# bottom.net
KiCad netlist of a schematic drawn in EAGLE
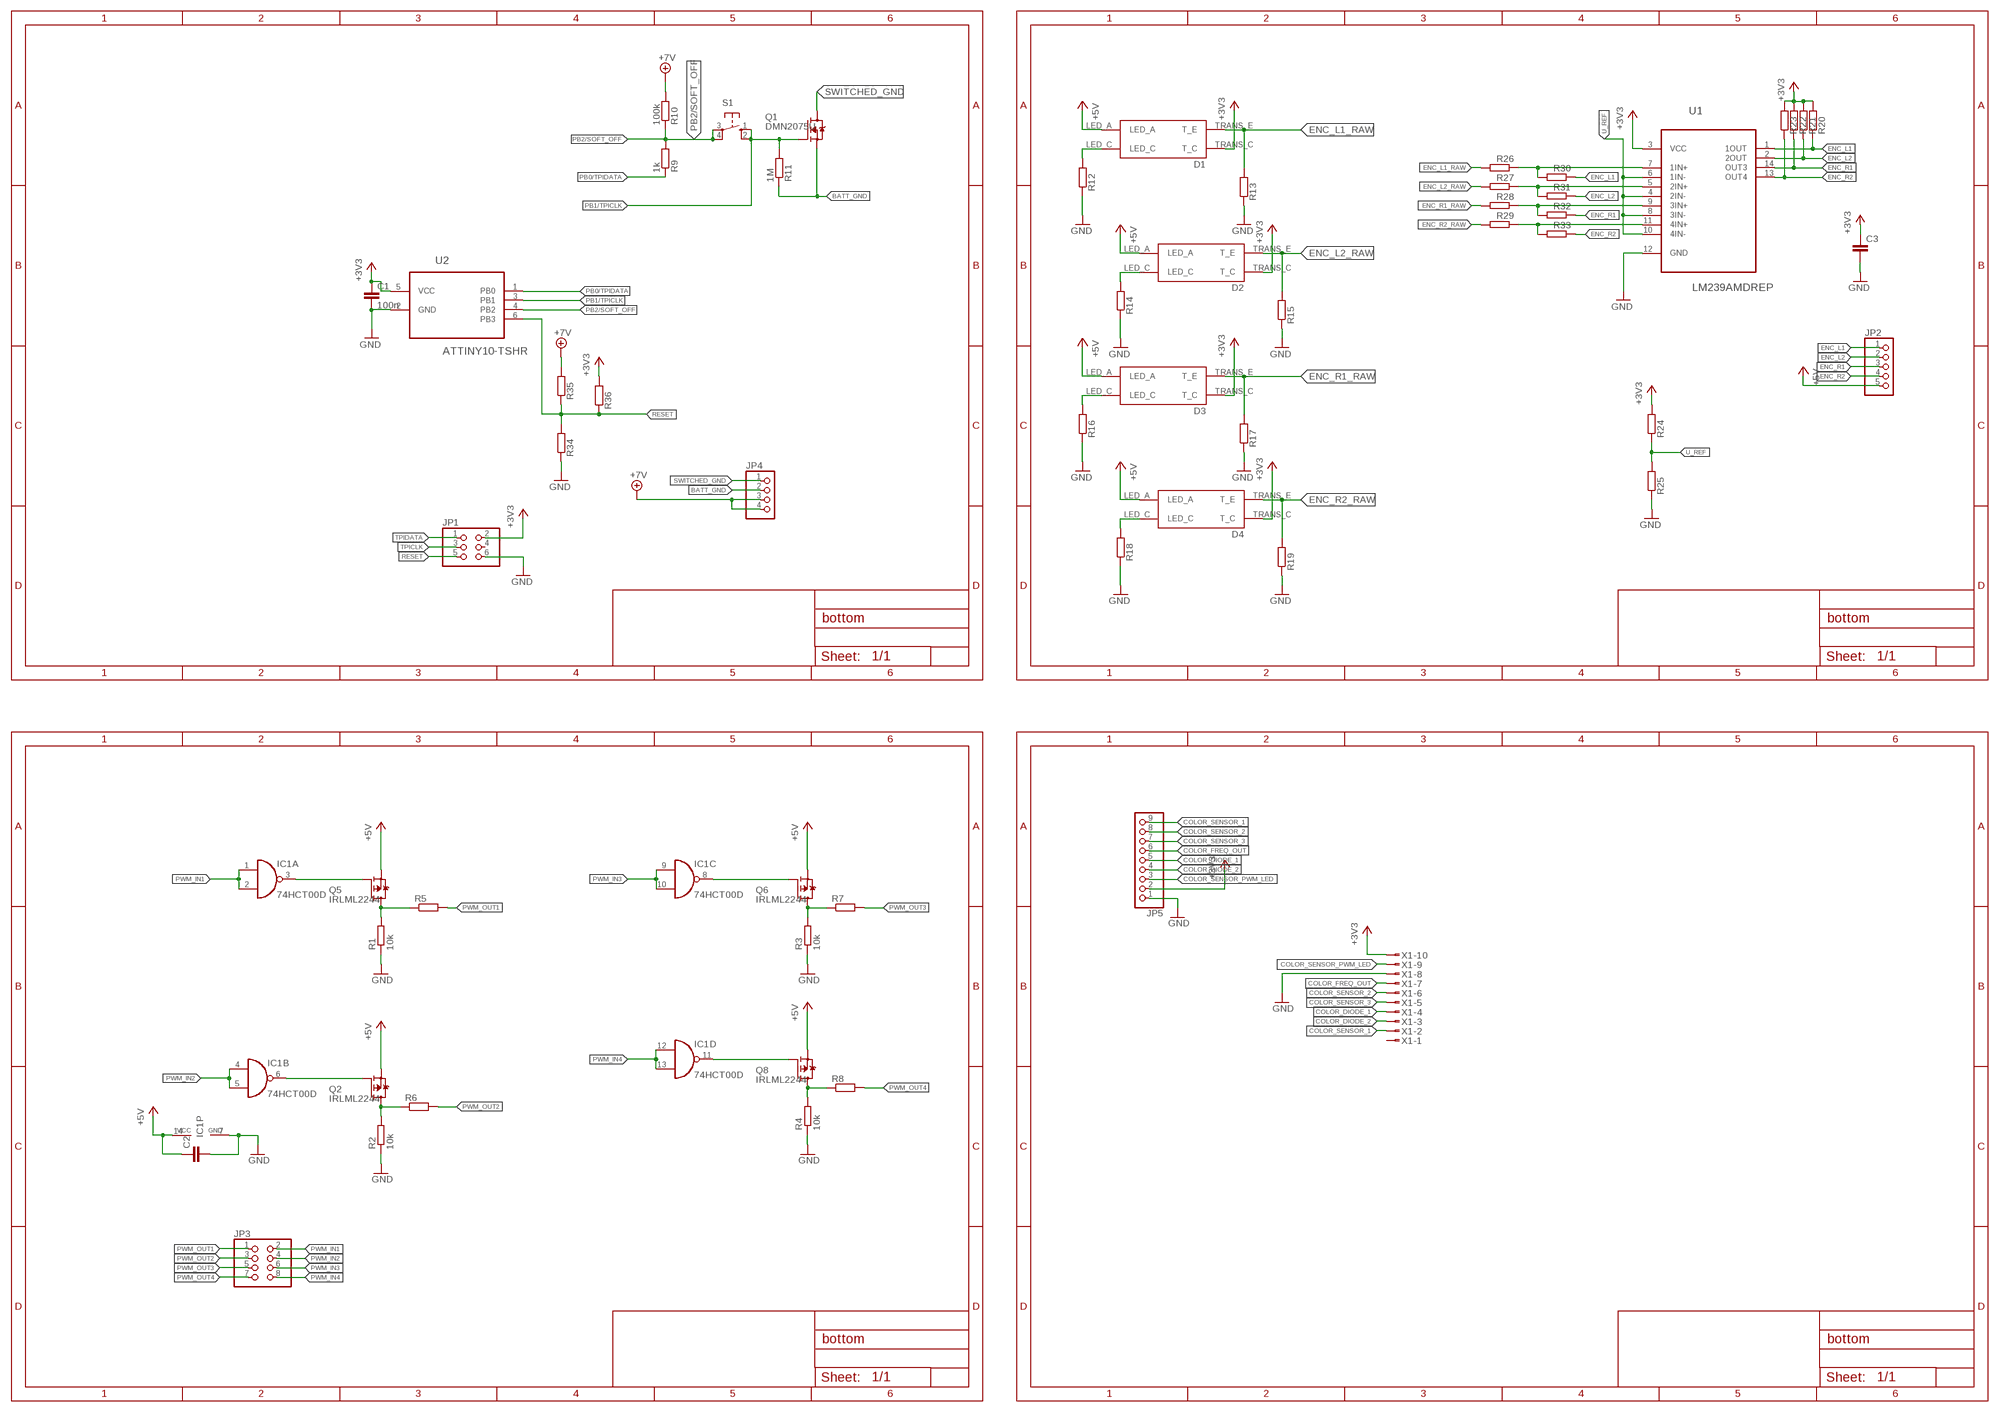
[diagram p0: schematic, sheet 1]

(export (version "E")
  (design (tool "Eeschema 10.0.6"))
  (components
    (comp (ref "C1")
      (value "100n")
      (footprint "eagle-import:C0603")
      (libsource (lib "eagle-import") (part "C-EUC0603"))
    )
    (comp (ref "C2")
      (value "C-EUC0603")
      (footprint "eagle-import:C0603")
      (libsource (lib "eagle-import") (part "C-EUC0603"))
    )
    (comp (ref "C3")
      (value "C-EUC0603")
      (footprint "eagle-import:C0603")
      (libsource (lib "eagle-import") (part "C-EUC0603"))
    )
    (comp (ref "D1")
      (value "CNY70")
      (footprint "eagle-import:CNY70")
      (libsource (lib "eagle-import") (part "CNY70"))
    )
    (comp (ref "D2")
      (value "CNY70")
      (footprint "eagle-import:CNY70")
      (libsource (lib "eagle-import") (part "CNY70"))
    )
    (comp (ref "D3")
      (value "CNY70")
      (footprint "eagle-import:CNY70")
      (libsource (lib "eagle-import") (part "CNY70"))
    )
    (comp (ref "D4")
      (value "CNY70")
      (footprint "eagle-import:CNY70")
      (libsource (lib "eagle-import") (part "CNY70"))
    )
    (comp (ref "IC1")
      (value "74HCT00D")
      (footprint "eagle-import:SO14")
      (libsource (lib "eagle-import") (part "7400DHCT"))
    )
    (comp (ref "JP1")
      (value "PINHD-2X3")
      (footprint "eagle-import:2X03")
      (libsource (lib "eagle-import") (part "PINHD-2X3"))
    )
    (comp (ref "JP2")
      (value "PINHD-1X5")
      (footprint "eagle-import:1X05")
      (libsource (lib "eagle-import") (part "PINHD-1X5"))
    )
    (comp (ref "JP3")
      (value "PINHD-2X4")
      (footprint "eagle-import:2X04")
      (libsource (lib "eagle-import") (part "PINHD-2X4"))
    )
    (comp (ref "JP4")
      (value "PINHD-1X4")
      (footprint "eagle-import:1X04")
      (libsource (lib "eagle-import") (part "PINHD-1X4"))
    )
    (comp (ref "JP5")
      (value "PINHD-1X9")
      (footprint "eagle-import:1X09")
      (libsource (lib "eagle-import") (part "PINHD-1X9"))
    )
    (comp (ref "Q1")
      (value "DMN2075U")
      (footprint "eagle-import:SOT95P240X112-3N")
      (libsource (lib "eagle-import") (part "DMN2075U"))
    )
    (comp (ref "Q2")
      (value "IRLML2244")
      (footprint "eagle-import:SOT95P240X112-3N")
      (libsource (lib "eagle-import") (part "IRLML2244"))
    )
    (comp (ref "Q5")
      (value "IRLML2244")
      (footprint "eagle-import:SOT95P240X112-3N")
      (libsource (lib "eagle-import") (part "IRLML2244"))
    )
    (comp (ref "Q6")
      (value "IRLML2244")
      (footprint "eagle-import:SOT95P240X112-3N")
      (libsource (lib "eagle-import") (part "IRLML2244"))
    )
    (comp (ref "Q8")
      (value "IRLML2244")
      (footprint "eagle-import:SOT95P240X112-3N")
      (libsource (lib "eagle-import") (part "IRLML2244"))
    )
    (comp (ref "R1")
      (value "10k")
      (footprint "eagle-import:R0603")
      (libsource (lib "eagle-import") (part "R-EU_R0603"))
    )
    (comp (ref "R2")
      (value "10k")
      (footprint "eagle-import:R0603")
      (libsource (lib "eagle-import") (part "R-EU_R0603"))
    )
    (comp (ref "R3")
      (value "10k")
      (footprint "eagle-import:R0603")
      (libsource (lib "eagle-import") (part "R-EU_R0603"))
    )
    (comp (ref "R4")
      (value "10k")
      (footprint "eagle-import:R0603")
      (libsource (lib "eagle-import") (part "R-EU_R0603"))
    )
    (comp (ref "R5")
      (value "R-EU_M0805")
      (footprint "eagle-import:M0805")
      (libsource (lib "eagle-import") (part "R-EU_M0805"))
    )
    (comp (ref "R6")
      (value "R-EU_M0805")
      (footprint "eagle-import:M0805")
      (libsource (lib "eagle-import") (part "R-EU_M0805"))
    )
    (comp (ref "R7")
      (value "R-EU_M0805")
      (footprint "eagle-import:M0805")
      (libsource (lib "eagle-import") (part "R-EU_M0805"))
    )
    (comp (ref "R8")
      (value "R-EU_M0805")
      (footprint "eagle-import:M0805")
      (libsource (lib "eagle-import") (part "R-EU_M0805"))
    )
    (comp (ref "R9")
      (value "1k")
      (footprint "eagle-import:M0805")
      (libsource (lib "eagle-import") (part "R-EU_M0805"))
    )
    (comp (ref "R10")
      (value "100k")
      (footprint "eagle-import:M0805")
      (libsource (lib "eagle-import") (part "R-EU_M0805"))
    )
    (comp (ref "R11")
      (value "1M")
      (footprint "eagle-import:M0805")
      (libsource (lib "eagle-import") (part "R-EU_M0805"))
    )
    (comp (ref "R12")
      (value "R-EU_R0805")
      (footprint "eagle-import:R0805")
      (libsource (lib "eagle-import") (part "R-EU_R0805"))
    )
    (comp (ref "R13")
      (value "R-EU_M0805")
      (footprint "eagle-import:M0805")
      (libsource (lib "eagle-import") (part "R-EU_M0805"))
    )
    (comp (ref "R14")
      (value "R-EU_M0805")
      (footprint "eagle-import:M0805")
      (libsource (lib "eagle-import") (part "R-EU_M0805"))
    )
    (comp (ref "R15")
      (value "R-EU_M0805")
      (footprint "eagle-import:M0805")
      (libsource (lib "eagle-import") (part "R-EU_M0805"))
    )
    (comp (ref "R16")
      (value "R-EU_M0805")
      (footprint "eagle-import:M0805")
      (libsource (lib "eagle-import") (part "R-EU_M0805"))
    )
    (comp (ref "R17")
      (value "R-EU_M0805")
      (footprint "eagle-import:M0805")
      (libsource (lib "eagle-import") (part "R-EU_M0805"))
    )
    (comp (ref "R18")
      (value "R-EU_M0805")
      (footprint "eagle-import:M0805")
      (libsource (lib "eagle-import") (part "R-EU_M0805"))
    )
    (comp (ref "R19")
      (value "R-EU_M0805")
      (footprint "eagle-import:M0805")
      (libsource (lib "eagle-import") (part "R-EU_M0805"))
    )
    (comp (ref "R20")
      (value "R-EU_M0805")
      (footprint "eagle-import:M0805")
      (libsource (lib "eagle-import") (part "R-EU_M0805"))
    )
    (comp (ref "R21")
      (value "R-EU_M0805")
      (footprint "eagle-import:M0805")
      (libsource (lib "eagle-import") (part "R-EU_M0805"))
    )
    (comp (ref "R22")
      (value "R-EU_M0805")
      (footprint "eagle-import:M0805")
      (libsource (lib "eagle-import") (part "R-EU_M0805"))
    )
    (comp (ref "R23")
      (value "R-EU_M0805")
      (footprint "eagle-import:M0805")
      (libsource (lib "eagle-import") (part "R-EU_M0805"))
    )
    (comp (ref "R24")
      (value "R-EU_M0805")
      (footprint "eagle-import:M0805")
      (libsource (lib "eagle-import") (part "R-EU_M0805"))
    )
    (comp (ref "R25")
      (value "R-EU_M0805")
      (footprint "eagle-import:M0805")
      (libsource (lib "eagle-import") (part "R-EU_M0805"))
    )
    (comp (ref "R26")
      (value "R-EU_M0805")
      (footprint "eagle-import:M0805")
      (libsource (lib "eagle-import") (part "R-EU_M0805"))
    )
    (comp (ref "R27")
      (value "R-EU_M0805")
      (footprint "eagle-import:M0805")
      (libsource (lib "eagle-import") (part "R-EU_M0805"))
    )
    (comp (ref "R28")
      (value "R-EU_M0805")
      (footprint "eagle-import:M0805")
      (libsource (lib "eagle-import") (part "R-EU_M0805"))
    )
    (comp (ref "R29")
      (value "R-EU_M0805")
      (footprint "eagle-import:M0805")
      (libsource (lib "eagle-import") (part "R-EU_M0805"))
    )
    (comp (ref "R30")
      (value "R-EU_M0805")
      (footprint "eagle-import:M0805")
      (libsource (lib "eagle-import") (part "R-EU_M0805"))
    )
    (comp (ref "R31")
      (value "R-EU_M0805")
      (footprint "eagle-import:M0805")
      (libsource (lib "eagle-import") (part "R-EU_M0805"))
    )
    (comp (ref "R32")
      (value "R-EU_M0805")
      (footprint "eagle-import:M0805")
      (libsource (lib "eagle-import") (part "R-EU_M0805"))
    )
    (comp (ref "R33")
      (value "R-EU_M0805")
      (footprint "eagle-import:M0805")
      (libsource (lib "eagle-import") (part "R-EU_M0805"))
    )
    (comp (ref "R34")
      (value "R-EU_M0805")
      (footprint "eagle-import:M0805")
      (libsource (lib "eagle-import") (part "R-EU_M0805"))
    )
    (comp (ref "R35")
      (value "R-EU_M0805")
      (footprint "eagle-import:M0805")
      (libsource (lib "eagle-import") (part "R-EU_M0805"))
    )
    (comp (ref "R36")
      (value "R-EU_M0805")
      (footprint "eagle-import:M0805")
      (libsource (lib "eagle-import") (part "R-EU_M0805"))
    )
    (comp (ref "S1")
      (value "10-XX")
      (footprint "eagle-import:B3F-10XX")
      (fields (field (name "MPN") "B3F-1000"))
      (libsource (lib "eagle-import") (part "10-XX"))
    )
    (comp (ref "U1")
      (value "LM239AMDREP")
      (footprint "eagle-import:SOIC127P600X175-14N")
      (libsource (lib "eagle-import") (part "LM239AMDREP"))
    )
    (comp (ref "U2")
      (value "ATTINY10-TSHR")
      (footprint "eagle-import:SOT95P280X145-6N")
      (libsource (lib "eagle-import") (part "ATTINY10-TSHR"))
    )
    (comp (ref "X1")
      (value "FTOP-10")
      (footprint "eagle-import:FTOP-10")
      (libsource (lib "eagle-import") (part "FTOP-10"))
    )
  )
  (nets
    (net (code "1") (name "+3V3") (class "Default")
      (node (ref "C1") (pin "1") (pinfunction "1_1") (pintype "passive"))
      (node (ref "C3") (pin "1") (pinfunction "1_1") (pintype "passive"))
      (node (ref "D1") (pin "TRANS_C") (pinfunction "T_C_TRANS_C") (pintype "bidirectional"))
      (node (ref "D2") (pin "TRANS_C") (pinfunction "T_C_TRANS_C") (pintype "bidirectional"))
      (node (ref "D3") (pin "TRANS_C") (pinfunction "T_C_TRANS_C") (pintype "bidirectional"))
      (node (ref "D4") (pin "TRANS_C") (pinfunction "T_C_TRANS_C") (pintype "bidirectional"))
      (node (ref "JP1") (pin "2") (pinfunction "2_2") (pintype "passive"))
      (node (ref "JP5") (pin "2") (pinfunction "2_2") (pintype "passive"))
      (node (ref "R20") (pin "2") (pinfunction "2_2") (pintype "passive"))
      (node (ref "R21") (pin "2") (pinfunction "2_2") (pintype "passive"))
      (node (ref "R22") (pin "2") (pinfunction "2_2") (pintype "passive"))
      (node (ref "R23") (pin "2") (pinfunction "2_2") (pintype "passive"))
      (node (ref "R24") (pin "2") (pinfunction "2_2") (pintype "passive"))
      (node (ref "R36") (pin "2") (pinfunction "2_2") (pintype "passive"))
      (node (ref "U1") (pin "3") (pinfunction "VCC_3") (pintype "power_in"))
      (node (ref "U2") (pin "5") (pinfunction "VCC_5") (pintype "power_in"))
      (node (ref "X1") (pin "10") (pinfunction "1_10") (pintype "passive"))
    )
    (net (code "2") (name "+5V") (class "Default")
      (node (ref "C2") (pin "1") (pinfunction "1_1") (pintype "passive"))
      (node (ref "D1") (pin "LED_A") (pinfunction "LED_A_LED_A") (pintype "bidirectional"))
      (node (ref "D2") (pin "LED_A") (pinfunction "LED_A_LED_A") (pintype "bidirectional"))
      (node (ref "D3") (pin "LED_A") (pinfunction "LED_A_LED_A") (pintype "bidirectional"))
      (node (ref "D4") (pin "LED_A") (pinfunction "LED_A_LED_A") (pintype "bidirectional"))
      (node (ref "IC1") (pin "14") (pinfunction "VCC_14") (pintype "power_in"))
      (node (ref "JP2") (pin "5") (pinfunction "5_5") (pintype "passive"))
      (node (ref "Q2") (pin "S") (pinfunction "S_S") (pintype "passive"))
      (node (ref "Q5") (pin "S") (pinfunction "S_S") (pintype "passive"))
      (node (ref "Q6") (pin "S") (pinfunction "S_S") (pintype "passive"))
      (node (ref "Q8") (pin "S") (pinfunction "S_S") (pintype "passive"))
    )
    (net (code "3") (name "+7V") (class "Default")
      (node (ref "JP4") (pin "3") (pinfunction "3_3") (pintype "passive"))
      (node (ref "JP4") (pin "4") (pinfunction "4_4") (pintype "passive"))
      (node (ref "R10") (pin "2") (pinfunction "2_2") (pintype "passive"))
      (node (ref "R35") (pin "2") (pinfunction "2_2") (pintype "passive"))
    )
    (net (code "4") (name "BATT_GND") (class "Default")
      (node (ref "JP4") (pin "2") (pinfunction "2_2") (pintype "passive"))
      (node (ref "Q1") (pin "S") (pinfunction "S_S") (pintype "passive"))
      (node (ref "R11") (pin "1") (pinfunction "1_1") (pintype "passive"))
    )
    (net (code "5") (name "COLOR_DIODE_1") (class "Default")
      (node (ref "JP5") (pin "5") (pinfunction "5_5") (pintype "passive"))
      (node (ref "X1") (pin "4") (pinfunction "1_4") (pintype "passive"))
    )
    (net (code "6") (name "COLOR_DIODE_2") (class "Default")
      (node (ref "JP5") (pin "4") (pinfunction "4_4") (pintype "passive"))
      (node (ref "X1") (pin "3") (pinfunction "1_3") (pintype "passive"))
    )
    (net (code "7") (name "COLOR_FREQ_OUT") (class "Default")
      (node (ref "JP5") (pin "6") (pinfunction "6_6") (pintype "passive"))
      (node (ref "X1") (pin "7") (pinfunction "1_7") (pintype "passive"))
    )
    (net (code "8") (name "COLOR_SENSOR_1") (class "Default")
      (node (ref "JP5") (pin "9") (pinfunction "9_9") (pintype "passive"))
      (node (ref "X1") (pin "2") (pinfunction "1_2") (pintype "passive"))
    )
    (net (code "9") (name "COLOR_SENSOR_2") (class "Default")
      (node (ref "JP5") (pin "8") (pinfunction "8_8") (pintype "passive"))
      (node (ref "X1") (pin "6") (pinfunction "1_6") (pintype "passive"))
    )
    (net (code "10") (name "COLOR_SENSOR_3") (class "Default")
      (node (ref "JP5") (pin "7") (pinfunction "7_7") (pintype "passive"))
      (node (ref "X1") (pin "5") (pinfunction "1_5") (pintype "passive"))
    )
    (net (code "11") (name "COLOR_SENSOR_PWM_LED") (class "Default")
      (node (ref "JP5") (pin "3") (pinfunction "3_3") (pintype "passive"))
      (node (ref "X1") (pin "9") (pinfunction "1_9") (pintype "passive"))
    )
    (net (code "12") (name "ENC_L1") (class "Default")
      (node (ref "JP2") (pin "1") (pinfunction "1_1") (pintype "passive"))
      (node (ref "R20") (pin "1") (pinfunction "1_1") (pintype "passive"))
      (node (ref "R30") (pin "1") (pinfunction "1_1") (pintype "passive"))
      (node (ref "U1") (pin "1") (pinfunction "1OUT_1") (pintype "output"))
    )
    (net (code "13") (name "ENC_L1_RAW") (class "Default")
      (node (ref "D1") (pin "TRANS_E") (pinfunction "T_E_TRANS_E") (pintype "bidirectional"))
      (node (ref "R13") (pin "2") (pinfunction "2_2") (pintype "passive"))
      (node (ref "R26") (pin "2") (pinfunction "2_2") (pintype "passive"))
    )
    (net (code "14") (name "ENC_L2") (class "Default")
      (node (ref "JP2") (pin "2") (pinfunction "2_2") (pintype "passive"))
      (node (ref "R21") (pin "1") (pinfunction "1_1") (pintype "passive"))
      (node (ref "R31") (pin "1") (pinfunction "1_1") (pintype "passive"))
      (node (ref "U1") (pin "2") (pinfunction "2OUT_2") (pintype "output"))
    )
    (net (code "15") (name "ENC_L2_RAW") (class "Default")
      (node (ref "D2") (pin "TRANS_E") (pinfunction "T_E_TRANS_E") (pintype "bidirectional"))
      (node (ref "R15") (pin "2") (pinfunction "2_2") (pintype "passive"))
      (node (ref "R27") (pin "2") (pinfunction "2_2") (pintype "passive"))
    )
    (net (code "16") (name "ENC_R1") (class "Default")
      (node (ref "JP2") (pin "3") (pinfunction "3_3") (pintype "passive"))
      (node (ref "R22") (pin "1") (pinfunction "1_1") (pintype "passive"))
      (node (ref "R32") (pin "1") (pinfunction "1_1") (pintype "passive"))
      (node (ref "U1") (pin "14") (pinfunction "OUT3_14") (pintype "output"))
    )
    (net (code "17") (name "ENC_R1_RAW") (class "Default")
      (node (ref "D3") (pin "TRANS_E") (pinfunction "T_E_TRANS_E") (pintype "bidirectional"))
      (node (ref "R17") (pin "2") (pinfunction "2_2") (pintype "passive"))
      (node (ref "R28") (pin "2") (pinfunction "2_2") (pintype "passive"))
    )
    (net (code "18") (name "ENC_R2") (class "Default")
      (node (ref "JP2") (pin "4") (pinfunction "4_4") (pintype "passive"))
      (node (ref "R23") (pin "1") (pinfunction "1_1") (pintype "passive"))
      (node (ref "R33") (pin "1") (pinfunction "1_1") (pintype "passive"))
      (node (ref "U1") (pin "13") (pinfunction "OUT4_13") (pintype "output"))
    )
    (net (code "19") (name "ENC_R2_RAW") (class "Default")
      (node (ref "D4") (pin "TRANS_E") (pinfunction "T_E_TRANS_E") (pintype "bidirectional"))
      (node (ref "R19") (pin "2") (pinfunction "2_2") (pintype "passive"))
      (node (ref "R29") (pin "2") (pinfunction "2_2") (pintype "passive"))
    )
    (net (code "20") (name "GND") (class "Default")
      (node (ref "C1") (pin "2") (pinfunction "2_2") (pintype "passive"))
      (node (ref "C2") (pin "2") (pinfunction "2_2") (pintype "passive"))
      (node (ref "C3") (pin "2") (pinfunction "2_2") (pintype "passive"))
      (node (ref "IC1") (pin "7") (pinfunction "GND_7") (pintype "power_in"))
      (node (ref "JP1") (pin "6") (pinfunction "6_6") (pintype "passive"))
      (node (ref "JP5") (pin "1") (pinfunction "1_1") (pintype "passive"))
      (node (ref "R1") (pin "1") (pinfunction "1_1") (pintype "passive"))
      (node (ref "R12") (pin "1") (pinfunction "1_1") (pintype "passive"))
      (node (ref "R13") (pin "1") (pinfunction "1_1") (pintype "passive"))
      (node (ref "R14") (pin "1") (pinfunction "1_1") (pintype "passive"))
      (node (ref "R15") (pin "1") (pinfunction "1_1") (pintype "passive"))
      (node (ref "R16") (pin "1") (pinfunction "1_1") (pintype "passive"))
      (node (ref "R17") (pin "1") (pinfunction "1_1") (pintype "passive"))
      (node (ref "R18") (pin "1") (pinfunction "1_1") (pintype "passive"))
      (node (ref "R19") (pin "1") (pinfunction "1_1") (pintype "passive"))
      (node (ref "R2") (pin "1") (pinfunction "1_1") (pintype "passive"))
      (node (ref "R25") (pin "1") (pinfunction "1_1") (pintype "passive"))
      (node (ref "R3") (pin "1") (pinfunction "1_1") (pintype "passive"))
      (node (ref "R34") (pin "1") (pinfunction "1_1") (pintype "passive"))
      (node (ref "R4") (pin "1") (pinfunction "1_1") (pintype "passive"))
      (node (ref "U1") (pin "12") (pinfunction "GND_12") (pintype "passive"))
      (node (ref "U2") (pin "2") (pinfunction "GND_2") (pintype "passive"))
      (node (ref "X1") (pin "8") (pinfunction "1_8") (pintype "passive"))
    )
    (net (code "21") (name "Net-(D1-PadLED_C)") (class "Default")
      (node (ref "D1") (pin "LED_C") (pinfunction "LED_C_LED_C") (pintype "bidirectional"))
      (node (ref "R12") (pin "2") (pinfunction "2_2") (pintype "passive"))
    )
    (net (code "22") (name "Net-(D2-PadLED_C)") (class "Default")
      (node (ref "D2") (pin "LED_C") (pinfunction "LED_C_LED_C") (pintype "bidirectional"))
      (node (ref "R14") (pin "2") (pinfunction "2_2") (pintype "passive"))
    )
    (net (code "23") (name "Net-(D3-PadLED_C)") (class "Default")
      (node (ref "D3") (pin "LED_C") (pinfunction "LED_C_LED_C") (pintype "bidirectional"))
      (node (ref "R16") (pin "2") (pinfunction "2_2") (pintype "passive"))
    )
    (net (code "24") (name "Net-(D4-PadLED_C)") (class "Default")
      (node (ref "D4") (pin "LED_C") (pinfunction "LED_C_LED_C") (pintype "bidirectional"))
      (node (ref "R18") (pin "2") (pinfunction "2_2") (pintype "passive"))
    )
    (net (code "25") (name "Net-(IC1A-O)") (class "Default")
      (node (ref "IC1") (pin "3") (pinfunction "O_3") (pintype "output"))
      (node (ref "Q5") (pin "G") (pinfunction "G_G") (pintype "passive"))
    )
    (net (code "26") (name "Net-(IC1B-O)") (class "Default")
      (node (ref "IC1") (pin "6") (pinfunction "O_6") (pintype "output"))
      (node (ref "Q2") (pin "G") (pinfunction "G_G") (pintype "passive"))
    )
    (net (code "27") (name "Net-(IC1C-O)") (class "Default")
      (node (ref "IC1") (pin "8") (pinfunction "O_8") (pintype "output"))
      (node (ref "Q6") (pin "G") (pinfunction "G_G") (pintype "passive"))
    )
    (net (code "28") (name "Net-(IC1D-O)") (class "Default")
      (node (ref "IC1") (pin "11") (pinfunction "O_11") (pintype "output"))
      (node (ref "Q8") (pin "G") (pinfunction "G_G") (pintype "passive"))
    )
    (net (code "29") (name "Net-(Q2-PadD)") (class "Default")
      (node (ref "Q2") (pin "D") (pinfunction "D_D") (pintype "passive"))
      (node (ref "R2") (pin "2") (pinfunction "2_2") (pintype "passive"))
      (node (ref "R6") (pin "1") (pinfunction "1_1") (pintype "passive"))
    )
    (net (code "30") (name "Net-(Q5-PadD)") (class "Default")
      (node (ref "Q5") (pin "D") (pinfunction "D_D") (pintype "passive"))
      (node (ref "R1") (pin "2") (pinfunction "2_2") (pintype "passive"))
      (node (ref "R5") (pin "1") (pinfunction "1_1") (pintype "passive"))
    )
    (net (code "31") (name "Net-(Q6-PadD)") (class "Default")
      (node (ref "Q6") (pin "D") (pinfunction "D_D") (pintype "passive"))
      (node (ref "R3") (pin "2") (pinfunction "2_2") (pintype "passive"))
      (node (ref "R7") (pin "1") (pinfunction "1_1") (pintype "passive"))
    )
    (net (code "32") (name "Net-(Q8-PadD)") (class "Default")
      (node (ref "Q8") (pin "D") (pinfunction "D_D") (pintype "passive"))
      (node (ref "R4") (pin "2") (pinfunction "2_2") (pintype "passive"))
      (node (ref "R8") (pin "1") (pinfunction "1_1") (pintype "passive"))
    )
    (net (code "33") (name "Net-(U1-1IN+)") (class "Default")
      (node (ref "R26") (pin "1") (pinfunction "1_1") (pintype "passive"))
      (node (ref "R30") (pin "2") (pinfunction "2_2") (pintype "passive"))
      (node (ref "U1") (pin "7") (pinfunction "1IN+_7") (pintype "input"))
    )
    (net (code "34") (name "Net-(U1-2IN+)") (class "Default")
      (node (ref "R27") (pin "1") (pinfunction "1_1") (pintype "passive"))
      (node (ref "R31") (pin "2") (pinfunction "2_2") (pintype "passive"))
      (node (ref "U1") (pin "5") (pinfunction "2IN+_5") (pintype "input"))
    )
    (net (code "35") (name "Net-(U1-3IN+)") (class "Default")
      (node (ref "R28") (pin "1") (pinfunction "1_1") (pintype "passive"))
      (node (ref "R32") (pin "2") (pinfunction "2_2") (pintype "passive"))
      (node (ref "U1") (pin "9") (pinfunction "3IN+_9") (pintype "input"))
    )
    (net (code "36") (name "Net-(U1-4IN+)") (class "Default")
      (node (ref "R29") (pin "1") (pinfunction "1_1") (pintype "passive"))
      (node (ref "R33") (pin "2") (pinfunction "2_2") (pintype "passive"))
      (node (ref "U1") (pin "11") (pinfunction "4IN+_11") (pintype "input"))
    )
    (net (code "37") (name "PB0{slash}TPIDATA") (class "Default")
      (node (ref "R9") (pin "1") (pinfunction "1_1") (pintype "passive"))
      (node (ref "U2") (pin "1") (pinfunction "PB0_1") (pintype "bidirectional"))
    )
    (net (code "38") (name "PB1{slash}TPICLK") (class "Default")
      (node (ref "Q1") (pin "G") (pinfunction "G_G") (pintype "passive"))
      (node (ref "R11") (pin "2") (pinfunction "2_2") (pintype "passive"))
      (node (ref "S1") (pin "1") (pinfunction "S_1") (pintype "passive"))
      (node (ref "S1") (pin "2") (pinfunction "S1_2") (pintype "passive"))
      (node (ref "U2") (pin "3") (pinfunction "PB1_3") (pintype "bidirectional"))
    )
    (net (code "39") (name "PB2{slash}SOFT_OFF") (class "Default")
      (node (ref "R10") (pin "1") (pinfunction "1_1") (pintype "passive"))
      (node (ref "R9") (pin "2") (pinfunction "2_2") (pintype "passive"))
      (node (ref "S1") (pin "3") (pinfunction "P_3") (pintype "passive"))
      (node (ref "S1") (pin "4") (pinfunction "P1_4") (pintype "passive"))
      (node (ref "U2") (pin "4") (pinfunction "PB2_4") (pintype "bidirectional"))
    )
    (net (code "40") (name "PWM_IN1") (class "Default")
      (node (ref "IC1") (pin "1") (pinfunction "I0_1") (pintype "input"))
      (node (ref "IC1") (pin "2") (pinfunction "I1_2") (pintype "input"))
      (node (ref "JP3") (pin "2") (pinfunction "2_2") (pintype "passive"))
    )
    (net (code "41") (name "PWM_IN2") (class "Default")
      (node (ref "IC1") (pin "4") (pinfunction "I0_4") (pintype "input"))
      (node (ref "IC1") (pin "5") (pinfunction "I1_5") (pintype "input"))
      (node (ref "JP3") (pin "4") (pinfunction "4_4") (pintype "passive"))
    )
    (net (code "42") (name "PWM_IN3") (class "Default")
      (node (ref "IC1") (pin "10") (pinfunction "I1_10") (pintype "input"))
      (node (ref "IC1") (pin "9") (pinfunction "I0_9") (pintype "input"))
      (node (ref "JP3") (pin "6") (pinfunction "6_6") (pintype "passive"))
    )
    (net (code "43") (name "PWM_IN4") (class "Default")
      (node (ref "IC1") (pin "12") (pinfunction "I0_12") (pintype "input"))
      (node (ref "IC1") (pin "13") (pinfunction "I1_13") (pintype "input"))
      (node (ref "JP3") (pin "8") (pinfunction "8_8") (pintype "passive"))
    )
    (net (code "44") (name "PWM_OUT1") (class "Default")
      (node (ref "JP3") (pin "1") (pinfunction "1_1") (pintype "passive"))
      (node (ref "R5") (pin "2") (pinfunction "2_2") (pintype "passive"))
    )
    (net (code "45") (name "PWM_OUT2") (class "Default")
      (node (ref "JP3") (pin "3") (pinfunction "3_3") (pintype "passive"))
      (node (ref "R6") (pin "2") (pinfunction "2_2") (pintype "passive"))
    )
    (net (code "46") (name "PWM_OUT3") (class "Default")
      (node (ref "JP3") (pin "5") (pinfunction "5_5") (pintype "passive"))
      (node (ref "R7") (pin "2") (pinfunction "2_2") (pintype "passive"))
    )
    (net (code "47") (name "PWM_OUT4") (class "Default")
      (node (ref "JP3") (pin "7") (pinfunction "7_7") (pintype "passive"))
      (node (ref "R8") (pin "2") (pinfunction "2_2") (pintype "passive"))
    )
    (net (code "48") (name "RESET") (class "Default")
      (node (ref "JP1") (pin "5") (pinfunction "5_5") (pintype "passive"))
      (node (ref "R34") (pin "2") (pinfunction "2_2") (pintype "passive"))
      (node (ref "R35") (pin "1") (pinfunction "1_1") (pintype "passive"))
      (node (ref "R36") (pin "1") (pinfunction "1_1") (pintype "passive"))
      (node (ref "U2") (pin "6") (pinfunction "PB3_6") (pintype "bidirectional"))
    )
    (net (code "49") (name "SWITCHED_GND") (class "Default")
      (node (ref "JP4") (pin "1") (pinfunction "1_1") (pintype "passive"))
      (node (ref "Q1") (pin "D") (pinfunction "D_D") (pintype "passive"))
    )
    (net (code "50") (name "TPICLK") (class "Default")
      (node (ref "JP1") (pin "3") (pinfunction "3_3") (pintype "passive"))
    )
    (net (code "51") (name "TPIDATA") (class "Default")
      (node (ref "JP1") (pin "1") (pinfunction "1_1") (pintype "passive"))
    )
    (net (code "52") (name "U_REF") (class "Default")
      (node (ref "R24") (pin "1") (pinfunction "1_1") (pintype "passive"))
      (node (ref "R25") (pin "2") (pinfunction "2_2") (pintype "passive"))
      (node (ref "U1") (pin "10") (pinfunction "4IN-_10") (pintype "input"))
      (node (ref "U1") (pin "4") (pinfunction "2IN-_4") (pintype "input"))
      (node (ref "U1") (pin "6") (pinfunction "1IN-_6") (pintype "input"))
      (node (ref "U1") (pin "8") (pinfunction "3IN-_8") (pintype "input"))
    )
    (net (code "53") (name "unconnected-(JP1-Pad4)") (class "Default")
      (node (ref "JP1") (pin "4") (pinfunction "4_4") (pintype "passive"))
    )
    (net (code "54") (name "unconnected-(X1-Pad1)") (class "Default")
      (node (ref "X1") (pin "1") (pinfunction "1_1") (pintype "passive"))
    )
  )
)
